# Sheet1.net
KiCad netlist of a schematic drawn in Altium Designer
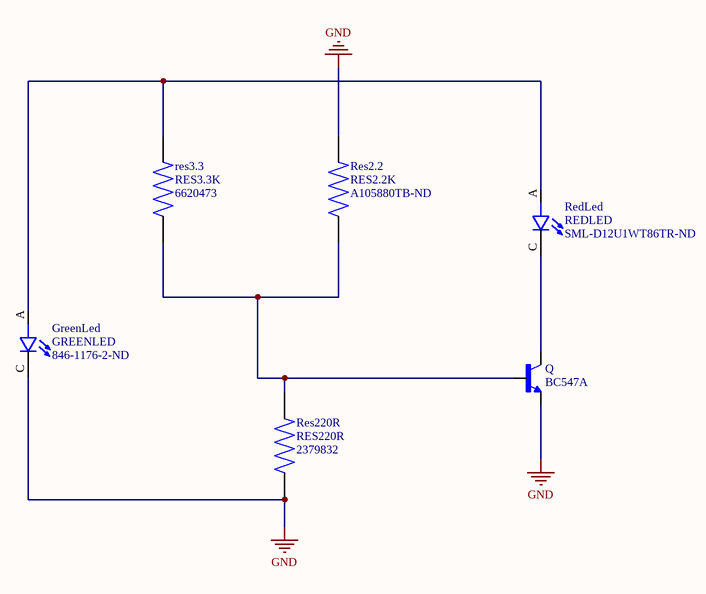
[diagram p0: Sheet1.SchDoc]

(export (version "E")
  (design (tool "Eeschema 10.0.6"))
  (components
    (comp (ref "GreenLed")
      (value "GREENLED")
      (footprint "LED_GREEN")
      (description "Green 565nm LED Indication - Discrete 2.2V 0603 (1608 Metric)")
      (fields
        (field (name "MF") "Rohm")
        (field (name "MP") "SML-D12FWT86")
        (field (name "SUPPLIER PART NUMBER 1") "846-1176-2-ND")
      )
      (libsource (lib "ERA6ARB332V") (part "GREENLED"))
    )
    (comp (ref "Q")
      (value "BC547A")
      (footprint "BC547B")
      (description "Bipolar _BJT_ Transistor NPN 45V 100mA 300MHz 500mW Through Hole TO-92-3")
      (fields (field (name "MF") "ON Semiconductor"))
      (libsource (lib "ERA6ARB332V") (part "BC547A"))
    )
    (comp (ref "RedLed")
      (value "REDLED")
      (footprint "LED_RED")
      (description "Red 620nm LED Indication - Discrete 2.2V 0603 _1608 Metric_")
      (fields
        (field (name "MP") "SML-D12U1WT86")
        (field (name "MF") "Rohm")
        (field (name "SUPPLIER PART NUMBER 1") "SML-D12U1WT86TR-ND")
      )
      (libsource (lib "ERA6ARB332V") (part "REDLED"))
    )
    (comp (ref "Res2.2")
      (value "RES2.2K")
      (footprint "RES2.2K")
      (description "RES 2.2K OHM 0.1% 1/8W 0805")
      (fields
        (field (name "MF") "Panasonic")
        (field (name "MP") "ERA-6APB222V")
        (field (name "SUPPLIER PART NUMBER 1") "A105880TB-ND")
      )
      (libsource (lib "ERA6ARB332V") (part "RES2.2K"))
    )
    (comp (ref "res3.3")
      (value "RES3.3K")
      (footprint "RES_3.3K")
      (description "RES 3.3K OHM 0.1% 1/8W 0805")
      (fields
        (field (name "MF") "Panasonic")
        (field (name "MP") "ERA6ARB332V")
        (field (name "SUPPLIER PART NUMBER 1") "6620473")
      )
      (libsource (lib "ERA6ARB332V") (part "RES3.3K"))
    )
    (comp (ref "Res220R")
      (value "RES220R")
      (footprint "RES_220R")
      (fields (field (name "MP") "ERJ-2RHD2200X") (field (name "SUPPLIER PART NUMBER 1") "2379832"))
      (libsource (lib "ERA6ARB332V") (part "RES220R"))
    )
  )
  (nets
    (net (code "1") (name "GND") (class "Default")
      (node (ref "GreenLed") (pin "C") (pinfunction "C_C") (pintype "passive"))
      (node (ref "Q") (pin "3") (pinfunction "E_3") (pintype "passive"))
      (node (ref "Res2.2") (pin "2") (pinfunction "2_2") (pintype "passive"))
      (node (ref "Res220R") (pin "1") (pinfunction "1_1") (pintype "passive"))
    )
    (net (code "2") (name "Net-(GreenLed-PadA)") (class "Default")
      (node (ref "GreenLed") (pin "A") (pinfunction "A_A") (pintype "passive"))
      (node (ref "RedLed") (pin "A") (pinfunction "A_A") (pintype "passive"))
      (node (ref "res3.3") (pin "2") (pinfunction "2_2") (pintype "passive"))
    )
    (net (code "3") (name "Net-(Q-B)") (class "Default")
      (node (ref "Q") (pin "2") (pinfunction "B_2") (pintype "passive"))
      (node (ref "Res2.2") (pin "1") (pinfunction "1_1") (pintype "passive"))
      (node (ref "Res220R") (pin "2") (pinfunction "2_2") (pintype "passive"))
      (node (ref "res3.3") (pin "1") (pinfunction "1_1") (pintype "passive"))
    )
    (net (code "4") (name "Net-(Q-C)") (class "Default")
      (node (ref "Q") (pin "1") (pinfunction "C_1") (pintype "passive"))
      (node (ref "RedLed") (pin "C") (pinfunction "C_C") (pintype "passive"))
    )
  )
)
